# sdc_prech_top_sheet.net
KiCad netlist of a schematic drawn in Altium Designer
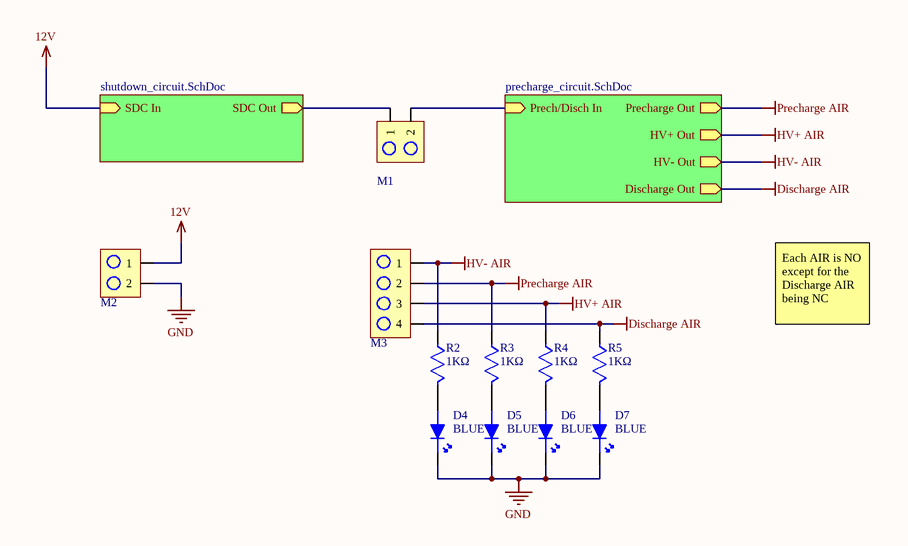
[diagram p0: sdc_prech_top_sheet.SchDoc]

(export (version "E")
  (design (tool "Eeschema 10.0.6"))
  (components
    (comp (ref "D4")
      (value "BLUE")
      (footprint "LED 0603")
      (description "LED BLUE CLEAR CHIP SMD")
      (fields
        (field (name "MANUFACTURER") "Vishay Lite-On")
        (field (name "MANUFACTURER PART NUMBER") "LTST-C191TBKT-5A")
      )
      (libsource (lib "sdc_prech_schlib") (part "LTST-C191TBKT-5A"))
    )
    (comp (ref "D5")
      (value "BLUE")
      (footprint "LED 0603")
      (description "LED BLUE CLEAR CHIP SMD")
      (fields
        (field (name "MANUFACTURER") "Vishay Lite-On")
        (field (name "MANUFACTURER PART NUMBER") "LTST-C191TBKT-5A")
      )
      (libsource (lib "sdc_prech_schlib") (part "LTST-C191TBKT-5A"))
    )
    (comp (ref "D6")
      (value "BLUE")
      (footprint "LED 0603")
      (description "LED BLUE CLEAR CHIP SMD")
      (fields
        (field (name "MANUFACTURER") "Vishay Lite-On")
        (field (name "MANUFACTURER PART NUMBER") "LTST-C191TBKT-5A")
      )
      (libsource (lib "sdc_prech_schlib") (part "LTST-C191TBKT-5A"))
    )
    (comp (ref "D7")
      (value "BLUE")
      (footprint "LED 0603")
      (description "LED BLUE CLEAR CHIP SMD")
      (fields
        (field (name "MANUFACTURER") "Vishay Lite-On")
        (field (name "MANUFACTURER PART NUMBER") "LTST-C191TBKT-5A")
      )
      (libsource (lib "sdc_prech_schlib") (part "LTST-C191TBKT-5A"))
    )
    (comp (ref "M1")
      (value "0436500228")
      (footprint "2-PIN MOLEX")
      (description "Conn Power HDR 2 POS 3mm Solder ST Thru-Hole 2 Terminal 1 Port Micro-Fit 3.0™ Tray")
      (fields (field (name "MANUFACTURER") "Molex"))
      (libsource (lib "sdc_prech_schlib") (part "0436500228"))
    )
    (comp (ref "M2")
      (value "0436500228")
      (footprint "2-PIN MOLEX")
      (description "Conn Power HDR 2 POS 3mm Solder ST Thru-Hole 2 Terminal 1 Port Micro-Fit 3.0™ Tray")
      (fields (field (name "MANUFACTURER") "Molex"))
      (libsource (lib "") (part "0436500228_1"))
    )
    (comp (ref "M3")
      (value "0436500428")
      (footprint "4-PIN MOLEX")
      (description "Conn Power HDR 4 POS 3mm Solder ST Thru-Hole 4 Terminal 1 Port Micro-Fit 3.0™ Tray")
      (fields (field (name "MANUFACTURER") "Molex"))
      (libsource (lib "sdc_prech_schlib") (part "0436500428"))
    )
    (comp (ref "R2")
      (value "1KΩ")
      (footprint "RESISTOR CRCW0603")
      (description "RES SMD 1K OHM 1% 1/10W 0603")
      (fields
        (field (name "MANUFACTURER") "Vishay Dale")
        (field (name "MANUFACTURER PART NUMBER") "CRCW06031K00FKEA")
      )
      (libsource (lib "sdc_prech_schlib") (part "CRCW06031K00FKEA"))
    )
    (comp (ref "R3")
      (value "1KΩ")
      (footprint "RESISTOR CRCW0603")
      (description "RES SMD 1K OHM 1% 1/10W 0603")
      (fields
        (field (name "MANUFACTURER") "Vishay Dale")
        (field (name "MANUFACTURER PART NUMBER") "CRCW06031K00FKEA")
      )
      (libsource (lib "sdc_prech_schlib") (part "CRCW06031K00FKEA"))
    )
    (comp (ref "R4")
      (value "1KΩ")
      (footprint "RESISTOR CRCW0603")
      (description "RES SMD 1K OHM 1% 1/10W 0603")
      (fields
        (field (name "MANUFACTURER") "Vishay Dale")
        (field (name "MANUFACTURER PART NUMBER") "CRCW06031K00FKEA")
      )
      (libsource (lib "sdc_prech_schlib") (part "CRCW06031K00FKEA"))
    )
    (comp (ref "R5")
      (value "1KΩ")
      (footprint "RESISTOR CRCW0603")
      (description "RES SMD 1K OHM 1% 1/10W 0603")
      (fields
        (field (name "MANUFACTURER") "Vishay Dale")
        (field (name "MANUFACTURER PART NUMBER") "CRCW06031K00FKEA")
      )
      (libsource (lib "sdc_prech_schlib") (part "CRCW06031K00FKEA"))
    )
  )
  (nets
    (net (code "1") (name "/Prech{slash}Disch In") (class "Default")
      (node (ref "M1") (pin "2") (pinfunction "2_2") (pintype "passive"))
    )
    (net (code "2") (name "/SDC Out") (class "Default")
      (node (ref "M1") (pin "1") (pinfunction "1_1") (pintype "passive"))
    )
    (net (code "3") (name "12V") (class "Default")
      (node (ref "M2") (pin "1") (pinfunction "1_1") (pintype "passive"))
    )
    (net (code "4") (name "Discharge AIR") (class "Default")
      (node (ref "M3") (pin "4") (pinfunction "4_4") (pintype "passive"))
      (node (ref "R5") (pin "1") (pinfunction "1_1") (pintype "passive"))
    )
    (net (code "5") (name "GND") (class "Default")
      (node (ref "D4") (pin "2") (pinfunction "2_2") (pintype "passive"))
      (node (ref "D5") (pin "2") (pinfunction "2_2") (pintype "passive"))
      (node (ref "D6") (pin "2") (pinfunction "2_2") (pintype "passive"))
      (node (ref "D7") (pin "2") (pinfunction "2_2") (pintype "passive"))
      (node (ref "M2") (pin "2") (pinfunction "2_2") (pintype "passive"))
    )
    (net (code "6") (name "HV+ AIR") (class "Default")
      (node (ref "M3") (pin "3") (pinfunction "3_3") (pintype "passive"))
      (node (ref "R4") (pin "1") (pinfunction "1_1") (pintype "passive"))
    )
    (net (code "7") (name "HV- AIR") (class "Default")
      (node (ref "M3") (pin "1") (pinfunction "1_1") (pintype "passive"))
      (node (ref "R2") (pin "1") (pinfunction "1_1") (pintype "passive"))
    )
    (net (code "8") (name "Net-(D4-Pad1)") (class "Default")
      (node (ref "D4") (pin "1") (pinfunction "1_1") (pintype "passive"))
      (node (ref "R2") (pin "2") (pinfunction "2_2") (pintype "passive"))
    )
    (net (code "9") (name "Net-(D5-Pad1)") (class "Default")
      (node (ref "D5") (pin "1") (pinfunction "1_1") (pintype "passive"))
      (node (ref "R3") (pin "2") (pinfunction "2_2") (pintype "passive"))
    )
    (net (code "10") (name "Net-(D6-Pad1)") (class "Default")
      (node (ref "D6") (pin "1") (pinfunction "1_1") (pintype "passive"))
      (node (ref "R4") (pin "2") (pinfunction "2_2") (pintype "passive"))
    )
    (net (code "11") (name "Net-(D7-Pad1)") (class "Default")
      (node (ref "D7") (pin "1") (pinfunction "1_1") (pintype "passive"))
      (node (ref "R5") (pin "2") (pinfunction "2_2") (pintype "passive"))
    )
    (net (code "12") (name "Precharge AIR") (class "Default")
      (node (ref "M3") (pin "2") (pinfunction "2_2") (pintype "passive"))
      (node (ref "R3") (pin "1") (pinfunction "1_1") (pintype "passive"))
    )
  )
)
